# StatusLEDs.net
KiCad netlist of a schematic drawn in Altium Designer
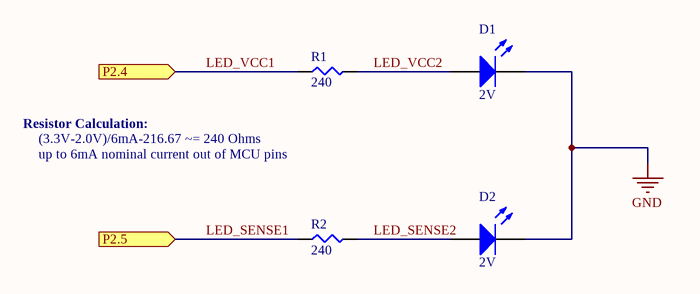
[diagram p0: StatusLEDs.SchDoc]

(export (version "E")
  (design (tool "Eeschema 10.0.6"))
  (components
    (comp (ref "D1")
      (value "2V")
      (footprint "0805_A")
      (description "SMD mono-color Chip LED, WL-SMCW, Bright Green")
      (fields
        (field (name "MANUFACTURER") "Wuerth Elektronik")
        (field (name "MANUFACTURER PART NUMBER") "150080VS75000")
      )
      (libsource (lib "Altium Content Vault") (part "WE-LED_K1A2-2"))
    )
    (comp (ref "D2")
      (value "2V")
      (footprint "0805_A")
      (description "SMD mono-color Chip LED, WL-SMCW, Bright Green")
      (fields
        (field (name "MANUFACTURER") "Wuerth Elektronik")
        (field (name "MANUFACTURER PART NUMBER") "150080VS75000")
      )
      (libsource (lib "Altium Content Vault") (part "WE-LED_K1A2-2"))
    )
    (comp (ref "R1")
      (value "240")
      (footprint "SMD-0805-RES")
      (description "RES SMD 240 OHM 1% 1/8W 0805")
      (fields
        (field (name "MANUFACTURER") "Panasonic Electronic Components")
        (field (name "MANUFACTURER PART NUMBER") "ERJ-6ENF2400V")
      )
      (libsource (lib "Panasonic_resistor_0805") (part "ERJ-6ENF2400V"))
    )
    (comp (ref "R2")
      (value "240")
      (footprint "SMD-0805-RES")
      (description "RES SMD 240 OHM 1% 1/8W 0805")
      (fields
        (field (name "MANUFACTURER") "Panasonic Electronic Components")
        (field (name "MANUFACTURER PART NUMBER") "ERJ-6ENF2400V")
      )
      (libsource (lib "Panasonic_resistor_0805") (part "ERJ-6ENF2400V"))
    )
  )
  (nets
    (net (code "1") (name "/LED_SENSE1") (class "Default")
      (node (ref "R2") (pin "1") (pinfunction "1_1") (pintype "passive"))
    )
    (net (code "2") (name "/LED_SENSE2") (class "Default")
      (node (ref "D2") (pin "2") (pinfunction "A_2") (pintype "passive"))
      (node (ref "R2") (pin "2") (pinfunction "2_2") (pintype "passive"))
    )
    (net (code "3") (name "/LED_VCC1") (class "Default")
      (node (ref "R1") (pin "1") (pinfunction "1_1") (pintype "passive"))
    )
    (net (code "4") (name "/LED_VCC2") (class "Default")
      (node (ref "D1") (pin "2") (pinfunction "A_2") (pintype "passive"))
      (node (ref "R1") (pin "2") (pinfunction "2_2") (pintype "passive"))
    )
    (net (code "5") (name "GND") (class "Default")
      (node (ref "D1") (pin "1") (pinfunction "K_1") (pintype "passive"))
      (node (ref "D2") (pin "1") (pinfunction "K_1") (pintype "passive"))
    )
  )
)
